# ATTiny85_LightBar.net
KiCad netlist of a schematic drawn in EAGLE
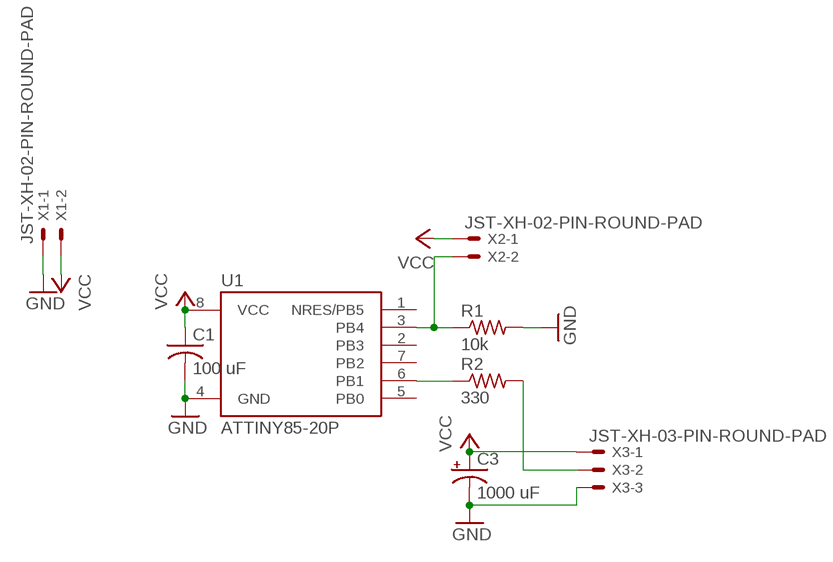
[diagram p0: schematic, sheet 1]

(export (version "E")
  (design (tool "Eeschema 10.0.6"))
  (components
    (comp (ref "C1")
      (value "100 uF")
      (footprint "eagle-import:C0805")
      (libsource (lib "eagle-import") (part "C-USC0805"))
    )
    (comp (ref "C3")
      (value "1000 uF")
      (footprint "eagle-import:E5-10,5")
      (libsource (lib "eagle-import") (part "CPOL-USE5-10.5"))
    )
    (comp (ref "R1")
      (value "10k")
      (footprint "eagle-import:R0805")
      (libsource (lib "eagle-import") (part "R-US_R0805"))
    )
    (comp (ref "R2")
      (value "330")
      (footprint "eagle-import:R0805")
      (libsource (lib "eagle-import") (part "R-US_R0805"))
    )
    (comp (ref "U1")
      (value "ATTINY85-20P")
      (footprint "eagle-import:PDIP08_300MIL")
      (libsource (lib "eagle-import") (part "ATTINY85P-20"))
    )
    (comp (ref "X1")
      (value "JST-XH-02-PIN-ROUND-PAD")
      (footprint "eagle-import:JST-XH-02-PACKAGE-ROUND-PAD")
      (libsource (lib "eagle-import") (part "JST-XH-02-PIN-ROUND-PAD"))
    )
    (comp (ref "X2")
      (value "JST-XH-02-PIN-ROUND-PAD")
      (footprint "eagle-import:JST-XH-02-PACKAGE-ROUND-PAD")
      (libsource (lib "eagle-import") (part "JST-XH-02-PIN-ROUND-PAD"))
    )
    (comp (ref "X3")
      (value "JST-XH-03-PIN-ROUND-PAD")
      (footprint "eagle-import:JST-XH-03-PACKAGE-ROUND-PAD")
      (libsource (lib "eagle-import") (part "JST-XH-03-PIN-ROUND-PAD"))
    )
  )
  (nets
    (net (code "1") (name "GND") (class "Default")
      (node (ref "C1") (pin "2") (pinfunction "2_2") (pintype "passive"))
      (node (ref "C3") (pin "-") (pinfunction "-_-") (pintype "passive"))
      (node (ref "R1") (pin "2") (pinfunction "2_2") (pintype "passive"))
      (node (ref "U1") (pin "4") (pinfunction "GND_4") (pintype "power_in"))
      (node (ref "X1") (pin "1") (pinfunction "S_1") (pintype "passive"))
      (node (ref "X3") (pin "3") (pinfunction "S_3") (pintype "passive"))
    )
    (net (code "2") (name "Net-(U1-PB1)") (class "Default")
      (node (ref "R2") (pin "1") (pinfunction "1_1") (pintype "passive"))
      (node (ref "U1") (pin "6") (pinfunction "PB1_6") (pintype "bidirectional"))
    )
    (net (code "3") (name "Net-(U1-PB4)") (class "Default")
      (node (ref "R1") (pin "1") (pinfunction "1_1") (pintype "passive"))
      (node (ref "U1") (pin "3") (pinfunction "PB4_3") (pintype "bidirectional"))
      (node (ref "X2") (pin "2") (pinfunction "S_2") (pintype "passive"))
    )
    (net (code "4") (name "Net-(X3B-S)") (class "Default")
      (node (ref "R2") (pin "2") (pinfunction "2_2") (pintype "passive"))
      (node (ref "X3") (pin "2") (pinfunction "S_2") (pintype "passive"))
    )
    (net (code "5") (name "VCC") (class "Default")
      (node (ref "C1") (pin "1") (pinfunction "1_1") (pintype "passive"))
      (node (ref "C3") (pin "+") (pinfunction "+_+") (pintype "passive"))
      (node (ref "U1") (pin "8") (pinfunction "VCC_8") (pintype "power_in"))
      (node (ref "X1") (pin "2") (pinfunction "S_2") (pintype "passive"))
      (node (ref "X2") (pin "1") (pinfunction "S_1") (pintype "passive"))
      (node (ref "X3") (pin "1") (pinfunction "S_1") (pintype "passive"))
    )
    (net (code "6") (name "unconnected-(U1-NRES{slash}PB5-Pad1)") (class "Default")
      (node (ref "U1") (pin "1") (pinfunction "NRES/PB5_1") (pintype "bidirectional"))
    )
    (net (code "7") (name "unconnected-(U1-PB0-Pad5)") (class "Default")
      (node (ref "U1") (pin "5") (pinfunction "PB0_5") (pintype "bidirectional"))
    )
    (net (code "8") (name "unconnected-(U1-PB2-Pad7)") (class "Default")
      (node (ref "U1") (pin "7") (pinfunction "PB2_7") (pintype "bidirectional"))
    )
    (net (code "9") (name "unconnected-(U1-PB3-Pad2)") (class "Default")
      (node (ref "U1") (pin "2") (pinfunction "PB3_2") (pintype "bidirectional"))
    )
  )
)
